# RFID_1.net
KiCad netlist of a schematic drawn in EAGLE
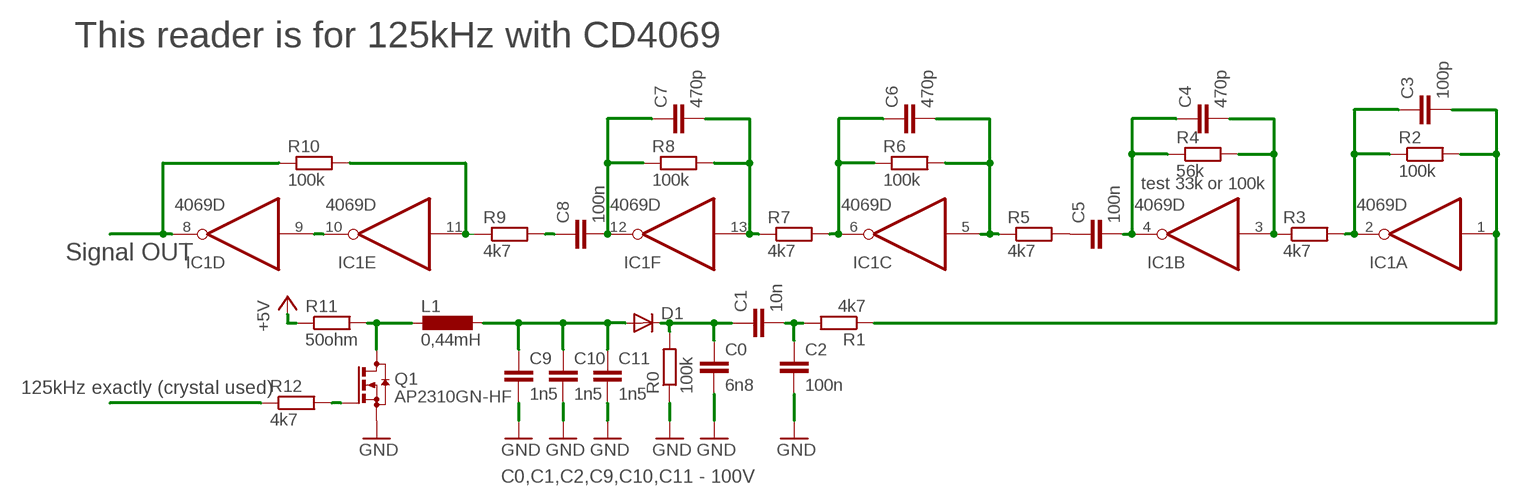
[diagram p0: schematic, sheet 1]

(export (version "E")
  (design (tool "Eeschema 10.0.6"))
  (components
    (comp (ref "C0")
      (value "6n8")
      (footprint "eagle-import:C0402")
      (libsource (lib "eagle-import") (part "C-EUC0402"))
    )
    (comp (ref "C1")
      (value "10n")
      (footprint "eagle-import:C0402")
      (libsource (lib "eagle-import") (part "C-EUC0402"))
    )
    (comp (ref "C2")
      (value "100n")
      (footprint "eagle-import:C0402")
      (libsource (lib "eagle-import") (part "C-EUC0402"))
    )
    (comp (ref "C3")
      (value "100p")
      (footprint "eagle-import:C0402")
      (libsource (lib "eagle-import") (part "C-EUC0402"))
    )
    (comp (ref "C4")
      (value "470p")
      (footprint "eagle-import:C0402")
      (libsource (lib "eagle-import") (part "C-EUC0402"))
    )
    (comp (ref "C5")
      (value "100n")
      (footprint "eagle-import:C0402")
      (libsource (lib "eagle-import") (part "C-EUC0402"))
    )
    (comp (ref "C6")
      (value "470p")
      (footprint "eagle-import:C0402")
      (libsource (lib "eagle-import") (part "C-EUC0402"))
    )
    (comp (ref "C7")
      (value "470p")
      (footprint "eagle-import:C0402")
      (libsource (lib "eagle-import") (part "C-EUC0402"))
    )
    (comp (ref "C8")
      (value "100n")
      (footprint "eagle-import:C0402")
      (libsource (lib "eagle-import") (part "C-EUC0402"))
    )
    (comp (ref "C9")
      (value "1n5")
      (footprint "eagle-import:C0402")
      (libsource (lib "eagle-import") (part "C-EUC0402"))
    )
    (comp (ref "C10")
      (value "1n5")
      (footprint "eagle-import:C0402")
      (libsource (lib "eagle-import") (part "C-EUC0402"))
    )
    (comp (ref "C11")
      (value "1n5")
      (footprint "eagle-import:C0402")
      (libsource (lib "eagle-import") (part "C-EUC0402"))
    )
    (comp (ref "D1")
      (value "DIODE-MINIMELF")
      (footprint "eagle-import:MINIMELF")
      (libsource (lib "eagle-import") (part "DIODE-MINIMELF"))
    )
    (comp (ref "IC1")
      (value "4069D")
      (footprint "eagle-import:SO14")
      (libsource (lib "eagle-import") (part "4069D"))
    )
    (comp (ref "L1")
      (value "0,44mH")
      (footprint "eagle-import:L1812")
      (libsource (lib "eagle-import") (part "L-EUL1812"))
    )
    (comp (ref "Q1")
      (value "AP2310GN-HF")
      (footprint "eagle-import:SOT23")
      (libsource (lib "eagle-import") (part "BSS123"))
    )
    (comp (ref "R0")
      (value "100k")
      (footprint "eagle-import:R0402")
      (libsource (lib "eagle-import") (part "R-EU_R0402"))
    )
    (comp (ref "R1")
      (value "4k7")
      (footprint "eagle-import:R0402")
      (libsource (lib "eagle-import") (part "R-EU_R0402"))
    )
    (comp (ref "R2")
      (value "100k")
      (footprint "eagle-import:R0402")
      (libsource (lib "eagle-import") (part "R-EU_R0402"))
    )
    (comp (ref "R3")
      (value "4k7")
      (footprint "eagle-import:R0402")
      (libsource (lib "eagle-import") (part "R-EU_R0402"))
    )
    (comp (ref "R4")
      (value "56k")
      (footprint "eagle-import:R0402")
      (libsource (lib "eagle-import") (part "R-EU_R0402"))
    )
    (comp (ref "R5")
      (value "4k7")
      (footprint "eagle-import:R0402")
      (libsource (lib "eagle-import") (part "R-EU_R0402"))
    )
    (comp (ref "R6")
      (value "100k")
      (footprint "eagle-import:R0402")
      (libsource (lib "eagle-import") (part "R-EU_R0402"))
    )
    (comp (ref "R7")
      (value "4k7")
      (footprint "eagle-import:R0402")
      (libsource (lib "eagle-import") (part "R-EU_R0402"))
    )
    (comp (ref "R8")
      (value "100k")
      (footprint "eagle-import:R0402")
      (libsource (lib "eagle-import") (part "R-EU_R0402"))
    )
    (comp (ref "R9")
      (value "4k7")
      (footprint "eagle-import:R0402")
      (libsource (lib "eagle-import") (part "R-EU_R0402"))
    )
    (comp (ref "R10")
      (value "100k")
      (footprint "eagle-import:R0402")
      (libsource (lib "eagle-import") (part "R-EU_R0402"))
    )
    (comp (ref "R11")
      (value "50ohm")
      (footprint "eagle-import:R1206")
      (libsource (lib "eagle-import") (part "R-EU_R1206"))
    )
    (comp (ref "R12")
      (value "4k7")
      (footprint "eagle-import:R0805")
      (libsource (lib "eagle-import") (part "R-EU_R0805"))
    )
  )
  (nets
    (net (code "1") (name "+5V") (class "Default")
      (node (ref "R11") (pin "1") (pinfunction "1_1") (pintype "passive"))
    )
    (net (code "2") (name "GND") (class "Default")
      (node (ref "C0") (pin "2") (pinfunction "2_2") (pintype "passive"))
      (node (ref "C10") (pin "2") (pinfunction "2_2") (pintype "passive"))
      (node (ref "C11") (pin "2") (pinfunction "2_2") (pintype "passive"))
      (node (ref "C2") (pin "2") (pinfunction "2_2") (pintype "passive"))
      (node (ref "C9") (pin "2") (pinfunction "2_2") (pintype "passive"))
      (node (ref "Q1") (pin "2") (pinfunction "S_2") (pintype "passive"))
      (node (ref "R0") (pin "1") (pinfunction "1_1") (pintype "passive"))
    )
    (net (code "3") (name "Net-(C0-Pad1)") (class "Default")
      (node (ref "C0") (pin "1") (pinfunction "1_1") (pintype "passive"))
      (node (ref "C1") (pin "1") (pinfunction "1_1") (pintype "passive"))
      (node (ref "D1") (pin "C") (pinfunction "C_C") (pintype "passive"))
      (node (ref "R0") (pin "2") (pinfunction "2_2") (pintype "passive"))
    )
    (net (code "4") (name "Net-(C1-Pad2)") (class "Default")
      (node (ref "C1") (pin "2") (pinfunction "2_2") (pintype "passive"))
      (node (ref "C2") (pin "1") (pinfunction "1_1") (pintype "passive"))
      (node (ref "R1") (pin "2") (pinfunction "2_2") (pintype "passive"))
    )
    (net (code "5") (name "Net-(C5-Pad1)") (class "Default")
      (node (ref "C5") (pin "1") (pinfunction "1_1") (pintype "passive"))
      (node (ref "R5") (pin "2") (pinfunction "2_2") (pintype "passive"))
    )
    (net (code "6") (name "Net-(C8-Pad1)") (class "Default")
      (node (ref "C8") (pin "1") (pinfunction "1_1") (pintype "passive"))
      (node (ref "R9") (pin "2") (pinfunction "2_2") (pintype "passive"))
    )
    (net (code "7") (name "Net-(C10-Pad1)") (class "Default")
      (node (ref "C10") (pin "1") (pinfunction "1_1") (pintype "passive"))
      (node (ref "C11") (pin "1") (pinfunction "1_1") (pintype "passive"))
      (node (ref "C9") (pin "1") (pinfunction "1_1") (pintype "passive"))
      (node (ref "D1") (pin "A") (pinfunction "A_A") (pintype "passive"))
      (node (ref "L1") (pin "1") (pinfunction "1_1") (pintype "passive"))
    )
    (net (code "8") (name "Net-(IC1A-I)") (class "Default")
      (node (ref "C3") (pin "2") (pinfunction "2_2") (pintype "passive"))
      (node (ref "IC1") (pin "1") (pinfunction "I_1") (pintype "input"))
      (node (ref "R1") (pin "1") (pinfunction "1_1") (pintype "passive"))
      (node (ref "R2") (pin "2") (pinfunction "2_2") (pintype "passive"))
    )
    (net (code "9") (name "Net-(IC1A-O)") (class "Default")
      (node (ref "C3") (pin "1") (pinfunction "1_1") (pintype "passive"))
      (node (ref "IC1") (pin "2") (pinfunction "O_2") (pintype "output"))
      (node (ref "R2") (pin "1") (pinfunction "1_1") (pintype "passive"))
      (node (ref "R3") (pin "2") (pinfunction "2_2") (pintype "passive"))
    )
    (net (code "10") (name "Net-(IC1B-I)") (class "Default")
      (node (ref "C4") (pin "2") (pinfunction "2_2") (pintype "passive"))
      (node (ref "IC1") (pin "3") (pinfunction "I_3") (pintype "input"))
      (node (ref "R3") (pin "1") (pinfunction "1_1") (pintype "passive"))
      (node (ref "R4") (pin "2") (pinfunction "2_2") (pintype "passive"))
    )
    (net (code "11") (name "Net-(IC1B-O)") (class "Default")
      (node (ref "C4") (pin "1") (pinfunction "1_1") (pintype "passive"))
      (node (ref "C5") (pin "2") (pinfunction "2_2") (pintype "passive"))
      (node (ref "IC1") (pin "4") (pinfunction "O_4") (pintype "output"))
      (node (ref "R4") (pin "1") (pinfunction "1_1") (pintype "passive"))
    )
    (net (code "12") (name "Net-(IC1C-I)") (class "Default")
      (node (ref "C6") (pin "2") (pinfunction "2_2") (pintype "passive"))
      (node (ref "IC1") (pin "5") (pinfunction "I_5") (pintype "input"))
      (node (ref "R5") (pin "1") (pinfunction "1_1") (pintype "passive"))
      (node (ref "R6") (pin "2") (pinfunction "2_2") (pintype "passive"))
    )
    (net (code "13") (name "Net-(IC1C-O)") (class "Default")
      (node (ref "C6") (pin "1") (pinfunction "1_1") (pintype "passive"))
      (node (ref "IC1") (pin "6") (pinfunction "O_6") (pintype "output"))
      (node (ref "R6") (pin "1") (pinfunction "1_1") (pintype "passive"))
      (node (ref "R7") (pin "2") (pinfunction "2_2") (pintype "passive"))
    )
    (net (code "14") (name "Net-(IC1D-I)") (class "Default")
      (node (ref "IC1") (pin "10") (pinfunction "O_10") (pintype "output"))
      (node (ref "IC1") (pin "9") (pinfunction "I_9") (pintype "input"))
    )
    (net (code "15") (name "Net-(IC1D-O)") (class "Default")
      (node (ref "IC1") (pin "8") (pinfunction "O_8") (pintype "output"))
      (node (ref "R10") (pin "1") (pinfunction "1_1") (pintype "passive"))
    )
    (net (code "16") (name "Net-(IC1E-I)") (class "Default")
      (node (ref "IC1") (pin "11") (pinfunction "I_11") (pintype "input"))
      (node (ref "R10") (pin "2") (pinfunction "2_2") (pintype "passive"))
      (node (ref "R9") (pin "1") (pinfunction "1_1") (pintype "passive"))
    )
    (net (code "17") (name "Net-(IC1F-I)") (class "Default")
      (node (ref "C7") (pin "2") (pinfunction "2_2") (pintype "passive"))
      (node (ref "IC1") (pin "13") (pinfunction "I_13") (pintype "input"))
      (node (ref "R7") (pin "1") (pinfunction "1_1") (pintype "passive"))
      (node (ref "R8") (pin "2") (pinfunction "2_2") (pintype "passive"))
    )
    (net (code "18") (name "Net-(IC1F-O)") (class "Default")
      (node (ref "C7") (pin "1") (pinfunction "1_1") (pintype "passive"))
      (node (ref "C8") (pin "2") (pinfunction "2_2") (pintype "passive"))
      (node (ref "IC1") (pin "12") (pinfunction "O_12") (pintype "output"))
      (node (ref "R8") (pin "1") (pinfunction "1_1") (pintype "passive"))
    )
    (net (code "19") (name "Net-(Q1-D)") (class "Default")
      (node (ref "L1") (pin "2") (pinfunction "2_2") (pintype "passive"))
      (node (ref "Q1") (pin "3") (pinfunction "D_3") (pintype "passive"))
      (node (ref "R11") (pin "2") (pinfunction "2_2") (pintype "passive"))
    )
    (net (code "20") (name "Net-(Q1-G)") (class "Default")
      (node (ref "Q1") (pin "1") (pinfunction "G_1") (pintype "passive"))
      (node (ref "R12") (pin "2") (pinfunction "2_2") (pintype "passive"))
    )
    (net (code "21") (name "unconnected-(R12-Pad1)") (class "Default")
      (node (ref "R12") (pin "1") (pinfunction "1_1") (pintype "passive"))
    )
  )
)
